# Ring_5_C.net
KiCad netlist of a schematic drawn in Altium Designer
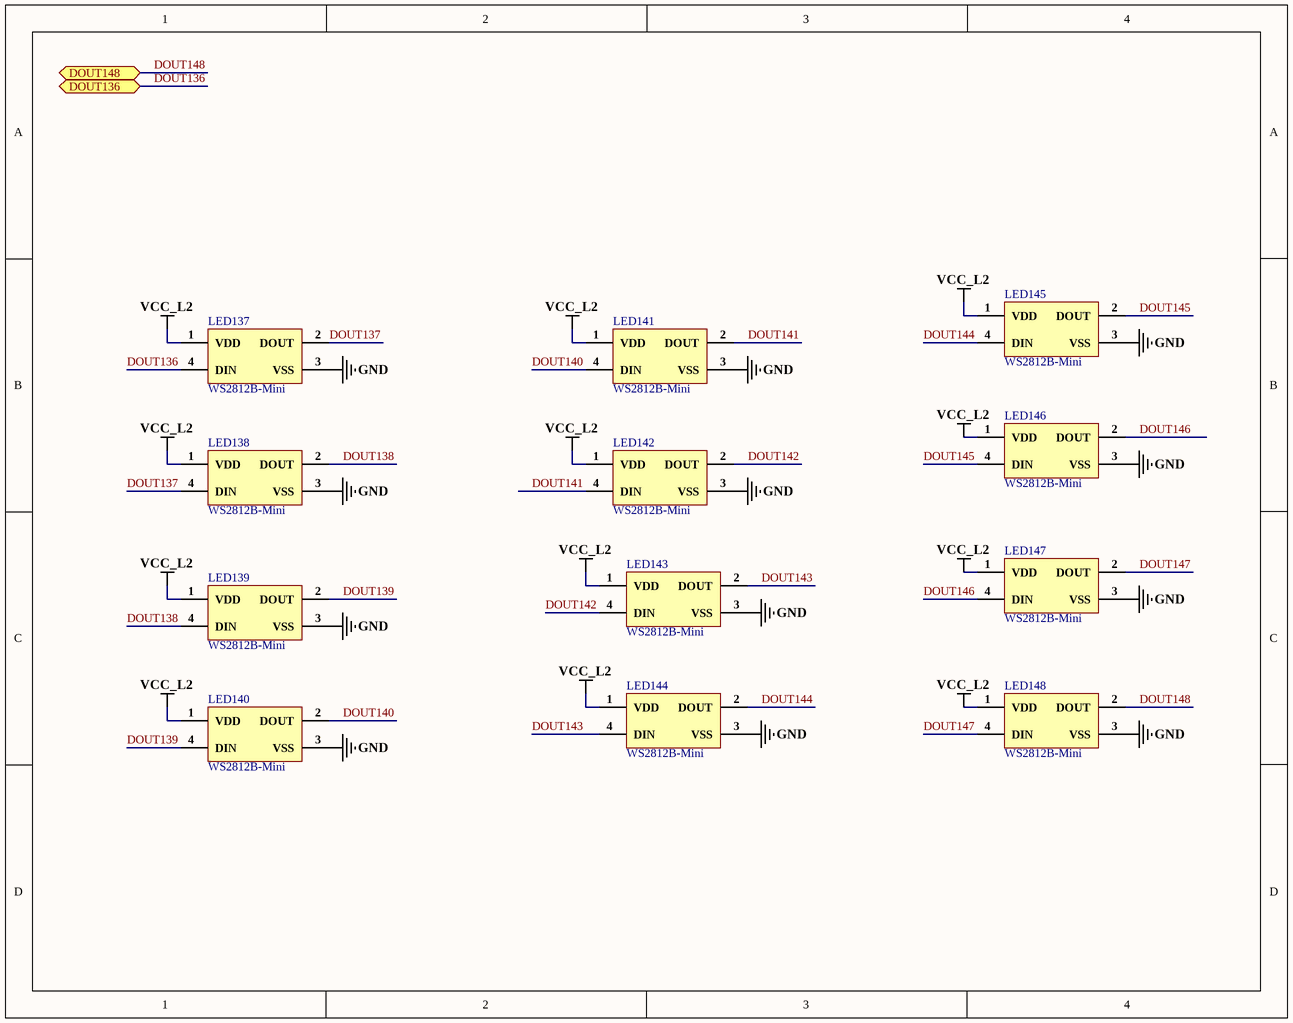
[diagram p0: Ring 5_C.SchDoc]

(export (version "E")
  (design (tool "Eeschema 10.0.6"))
  (components
    (comp (ref "LED137")
      (value "WS2812B-Mini")
      (footprint "WS2812B-Mini")
      (description "SMD,3.5x3.5mm Light Emitting Diodes (LED) RoHS")
      (fields (field (name "MANUFACTURER") "Worldsemi"))
      (libsource (lib "TT_IntLib") (part "WS2812B-Mini"))
    )
    (comp (ref "LED138")
      (value "WS2812B-Mini")
      (footprint "WS2812B-Mini")
      (description "SMD,3.5x3.5mm Light Emitting Diodes (LED) RoHS")
      (fields (field (name "MANUFACTURER") "Worldsemi"))
      (libsource (lib "TT_IntLib") (part "WS2812B-Mini"))
    )
    (comp (ref "LED139")
      (value "WS2812B-Mini")
      (footprint "WS2812B-Mini")
      (description "SMD,3.5x3.5mm Light Emitting Diodes (LED) RoHS")
      (fields (field (name "MANUFACTURER") "Worldsemi"))
      (libsource (lib "TT_IntLib") (part "WS2812B-Mini"))
    )
    (comp (ref "LED140")
      (value "WS2812B-Mini")
      (footprint "WS2812B-Mini")
      (description "SMD,3.5x3.5mm Light Emitting Diodes (LED) RoHS")
      (fields (field (name "MANUFACTURER") "Worldsemi"))
      (libsource (lib "TT_IntLib") (part "WS2812B-Mini"))
    )
    (comp (ref "LED141")
      (value "WS2812B-Mini")
      (footprint "WS2812B-Mini")
      (description "SMD,3.5x3.5mm Light Emitting Diodes (LED) RoHS")
      (fields (field (name "MANUFACTURER") "Worldsemi"))
      (libsource (lib "TT_IntLib") (part "WS2812B-Mini"))
    )
    (comp (ref "LED142")
      (value "WS2812B-Mini")
      (footprint "WS2812B-Mini")
      (description "SMD,3.5x3.5mm Light Emitting Diodes (LED) RoHS")
      (fields (field (name "MANUFACTURER") "Worldsemi"))
      (libsource (lib "TT_IntLib") (part "WS2812B-Mini"))
    )
    (comp (ref "LED143")
      (value "WS2812B-Mini")
      (footprint "WS2812B-Mini")
      (description "SMD,3.5x3.5mm Light Emitting Diodes (LED) RoHS")
      (fields (field (name "MANUFACTURER") "Worldsemi"))
      (libsource (lib "TT_IntLib") (part "WS2812B-Mini"))
    )
    (comp (ref "LED144")
      (value "WS2812B-Mini")
      (footprint "WS2812B-Mini")
      (description "SMD,3.5x3.5mm Light Emitting Diodes (LED) RoHS")
      (fields (field (name "MANUFACTURER") "Worldsemi"))
      (libsource (lib "TT_IntLib") (part "WS2812B-Mini"))
    )
    (comp (ref "LED145")
      (value "WS2812B-Mini")
      (footprint "WS2812B-Mini")
      (description "SMD,3.5x3.5mm Light Emitting Diodes (LED) RoHS")
      (fields (field (name "MANUFACTURER") "Worldsemi"))
      (libsource (lib "TT_IntLib") (part "WS2812B-Mini"))
    )
    (comp (ref "LED146")
      (value "WS2812B-Mini")
      (footprint "WS2812B-Mini")
      (description "SMD,3.5x3.5mm Light Emitting Diodes (LED) RoHS")
      (fields (field (name "MANUFACTURER") "Worldsemi"))
      (libsource (lib "TT_IntLib") (part "WS2812B-Mini"))
    )
    (comp (ref "LED147")
      (value "WS2812B-Mini")
      (footprint "WS2812B-Mini")
      (description "SMD,3.5x3.5mm Light Emitting Diodes (LED) RoHS")
      (fields (field (name "MANUFACTURER") "Worldsemi"))
      (libsource (lib "TT_IntLib") (part "WS2812B-Mini"))
    )
    (comp (ref "LED148")
      (value "WS2812B-Mini")
      (footprint "WS2812B-Mini")
      (description "SMD,3.5x3.5mm Light Emitting Diodes (LED) RoHS")
      (fields (field (name "MANUFACTURER") "Worldsemi"))
      (libsource (lib "TT_IntLib") (part "WS2812B-Mini"))
    )
  )
  (nets
    (net (code "1") (name "/DOUT136") (class "Default")
      (node (ref "LED137") (pin "4") (pinfunction "DIN_4") (pintype "passive"))
    )
    (net (code "2") (name "/DOUT137") (class "Default")
      (node (ref "LED137") (pin "2") (pinfunction "DOUT_2") (pintype "passive"))
      (node (ref "LED138") (pin "4") (pinfunction "DIN_4") (pintype "passive"))
    )
    (net (code "3") (name "/DOUT138") (class "Default")
      (node (ref "LED138") (pin "2") (pinfunction "DOUT_2") (pintype "passive"))
      (node (ref "LED139") (pin "4") (pinfunction "DIN_4") (pintype "passive"))
    )
    (net (code "4") (name "/DOUT139") (class "Default")
      (node (ref "LED139") (pin "2") (pinfunction "DOUT_2") (pintype "passive"))
      (node (ref "LED140") (pin "4") (pinfunction "DIN_4") (pintype "passive"))
    )
    (net (code "5") (name "/DOUT140") (class "Default")
      (node (ref "LED140") (pin "2") (pinfunction "DOUT_2") (pintype "passive"))
      (node (ref "LED141") (pin "4") (pinfunction "DIN_4") (pintype "passive"))
    )
    (net (code "6") (name "/DOUT141") (class "Default")
      (node (ref "LED141") (pin "2") (pinfunction "DOUT_2") (pintype "passive"))
      (node (ref "LED142") (pin "4") (pinfunction "DIN_4") (pintype "passive"))
    )
    (net (code "7") (name "/DOUT142") (class "Default")
      (node (ref "LED142") (pin "2") (pinfunction "DOUT_2") (pintype "passive"))
      (node (ref "LED143") (pin "4") (pinfunction "DIN_4") (pintype "passive"))
    )
    (net (code "8") (name "/DOUT143") (class "Default")
      (node (ref "LED143") (pin "2") (pinfunction "DOUT_2") (pintype "passive"))
      (node (ref "LED144") (pin "4") (pinfunction "DIN_4") (pintype "passive"))
    )
    (net (code "9") (name "/DOUT144") (class "Default")
      (node (ref "LED144") (pin "2") (pinfunction "DOUT_2") (pintype "passive"))
      (node (ref "LED145") (pin "4") (pinfunction "DIN_4") (pintype "passive"))
    )
    (net (code "10") (name "/DOUT145") (class "Default")
      (node (ref "LED145") (pin "2") (pinfunction "DOUT_2") (pintype "passive"))
      (node (ref "LED146") (pin "4") (pinfunction "DIN_4") (pintype "passive"))
    )
    (net (code "11") (name "/DOUT146") (class "Default")
      (node (ref "LED146") (pin "2") (pinfunction "DOUT_2") (pintype "passive"))
      (node (ref "LED147") (pin "4") (pinfunction "DIN_4") (pintype "passive"))
    )
    (net (code "12") (name "/DOUT147") (class "Default")
      (node (ref "LED147") (pin "2") (pinfunction "DOUT_2") (pintype "passive"))
      (node (ref "LED148") (pin "4") (pinfunction "DIN_4") (pintype "passive"))
    )
    (net (code "13") (name "/DOUT148") (class "Default")
      (node (ref "LED148") (pin "2") (pinfunction "DOUT_2") (pintype "passive"))
    )
    (net (code "14") (name "GND") (class "Default")
      (node (ref "LED137") (pin "3") (pinfunction "VSS_3") (pintype "passive"))
      (node (ref "LED138") (pin "3") (pinfunction "VSS_3") (pintype "passive"))
      (node (ref "LED139") (pin "3") (pinfunction "VSS_3") (pintype "passive"))
      (node (ref "LED140") (pin "3") (pinfunction "VSS_3") (pintype "passive"))
      (node (ref "LED141") (pin "3") (pinfunction "VSS_3") (pintype "passive"))
      (node (ref "LED142") (pin "3") (pinfunction "VSS_3") (pintype "passive"))
      (node (ref "LED143") (pin "3") (pinfunction "VSS_3") (pintype "passive"))
      (node (ref "LED144") (pin "3") (pinfunction "VSS_3") (pintype "passive"))
      (node (ref "LED145") (pin "3") (pinfunction "VSS_3") (pintype "passive"))
      (node (ref "LED146") (pin "3") (pinfunction "VSS_3") (pintype "passive"))
      (node (ref "LED147") (pin "3") (pinfunction "VSS_3") (pintype "passive"))
      (node (ref "LED148") (pin "3") (pinfunction "VSS_3") (pintype "passive"))
    )
    (net (code "15") (name "VCC_L2") (class "Default")
      (node (ref "LED137") (pin "1") (pinfunction "VDD_1") (pintype "passive"))
      (node (ref "LED138") (pin "1") (pinfunction "VDD_1") (pintype "passive"))
      (node (ref "LED139") (pin "1") (pinfunction "VDD_1") (pintype "passive"))
      (node (ref "LED140") (pin "1") (pinfunction "VDD_1") (pintype "passive"))
      (node (ref "LED141") (pin "1") (pinfunction "VDD_1") (pintype "passive"))
      (node (ref "LED142") (pin "1") (pinfunction "VDD_1") (pintype "passive"))
      (node (ref "LED143") (pin "1") (pinfunction "VDD_1") (pintype "passive"))
      (node (ref "LED144") (pin "1") (pinfunction "VDD_1") (pintype "passive"))
      (node (ref "LED145") (pin "1") (pinfunction "VDD_1") (pintype "passive"))
      (node (ref "LED146") (pin "1") (pinfunction "VDD_1") (pintype "passive"))
      (node (ref "LED147") (pin "1") (pinfunction "VDD_1") (pintype "passive"))
      (node (ref "LED148") (pin "1") (pinfunction "VDD_1") (pintype "passive"))
    )
  )
)
